# CurrentAmplifier_V2.net
KiCad netlist of a schematic drawn in EAGLE
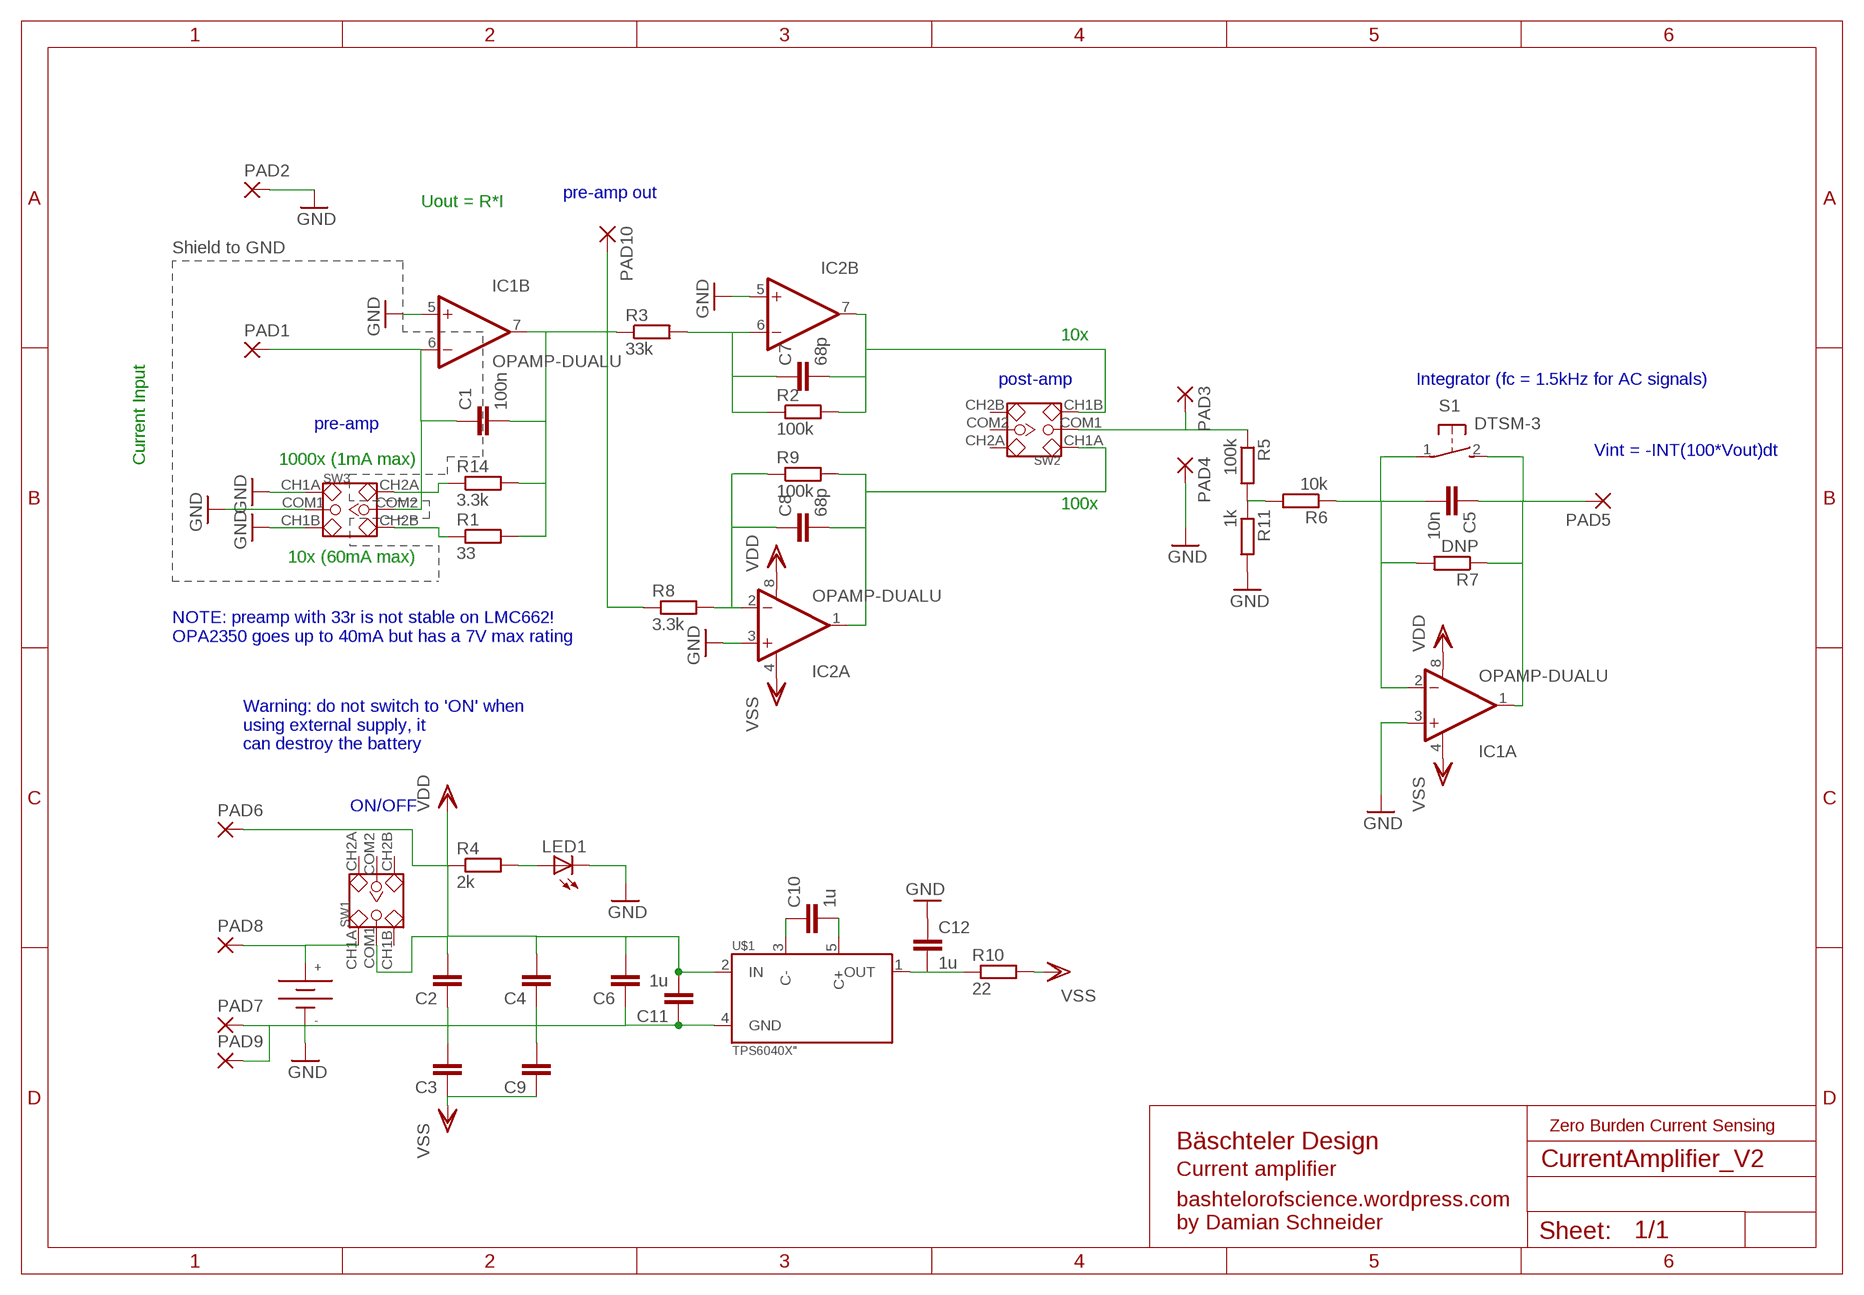
[diagram p0: schematic, sheet 1]

(export (version "E")
  (design (tool "Eeschema 10.0.6"))
  (components
    (comp (ref "C1")
      (value "100n")
      (footprint "eagle-import:C0805K")
      (libsource (lib "eagle-import") (part "C-EUC0805K"))
    )
    (comp (ref "C2")
      (value "C-EUC0805")
      (footprint "eagle-import:C0805")
      (libsource (lib "eagle-import") (part "C-EUC0805"))
    )
    (comp (ref "C3")
      (value "C-EUC0805")
      (footprint "eagle-import:C0805")
      (libsource (lib "eagle-import") (part "C-EUC0805"))
    )
    (comp (ref "C4")
      (value "C-EUC0805")
      (footprint "eagle-import:C0805")
      (libsource (lib "eagle-import") (part "C-EUC0805"))
    )
    (comp (ref "C5")
      (value "10n")
      (footprint "eagle-import:C0805K")
      (libsource (lib "eagle-import") (part "C-EUC0805K"))
    )
    (comp (ref "C6")
      (value "C-EUC1206")
      (footprint "eagle-import:C1206")
      (libsource (lib "eagle-import") (part "C-EUC1206"))
    )
    (comp (ref "C7")
      (value "68p")
      (footprint "eagle-import:C0603")
      (libsource (lib "eagle-import") (part "C-EUC0603"))
    )
    (comp (ref "C8")
      (value "68p")
      (footprint "eagle-import:C0603")
      (libsource (lib "eagle-import") (part "C-EUC0603"))
    )
    (comp (ref "C9")
      (value "C-EUC1206")
      (footprint "eagle-import:C1206")
      (libsource (lib "eagle-import") (part "C-EUC1206"))
    )
    (comp (ref "C10")
      (value "1u")
      (footprint "eagle-import:C0603")
      (libsource (lib "eagle-import") (part "C-EUC0603"))
    )
    (comp (ref "C11")
      (value "1u")
      (footprint "eagle-import:C0603")
      (libsource (lib "eagle-import") (part "C-EUC0603"))
    )
    (comp (ref "C12")
      (value "1u")
      (footprint "eagle-import:C0603")
      (libsource (lib "eagle-import") (part "C-EUC0603"))
    )
    (comp (ref "CR1")
      (value "DX_CR2032HANDSOLDER")
      (footprint "eagle-import:DX_CR2032_SMD_HANDSOLDER")
      (libsource (lib "eagle-import") (part "DX_CR2032HANDSOLDER"))
    )
    (comp (ref "IC1")
      (value "OPAMP-DUALU")
      (footprint "eagle-import:SO08")
      (libsource (lib "eagle-import") (part "OPAMP-DUALU"))
    )
    (comp (ref "IC2")
      (value "OPAMP-DUALU")
      (footprint "eagle-import:SO08")
      (libsource (lib "eagle-import") (part "OPAMP-DUALU"))
    )
    (comp (ref "LED1")
      (value "LEDCHIP-LED0805")
      (footprint "eagle-import:CHIP-LED0805")
      (libsource (lib "eagle-import") (part "LEDCHIP-LED0805"))
    )
    (comp (ref "PAD1")
      (value "1,6/0,9")
      (footprint "eagle-import:1,6_0,9")
      (libsource (lib "eagle-import") (part "1,6/0,9"))
    )
    (comp (ref "PAD2")
      (value "1,6/0,9")
      (footprint "eagle-import:1,6_0,9")
      (libsource (lib "eagle-import") (part "1,6/0,9"))
    )
    (comp (ref "PAD3")
      (value "1,6/0,9")
      (footprint "eagle-import:1,6_0,9")
      (libsource (lib "eagle-import") (part "1,6/0,9"))
    )
    (comp (ref "PAD4")
      (value "1,6/0,9")
      (footprint "eagle-import:1,6_0,9")
      (libsource (lib "eagle-import") (part "1,6/0,9"))
    )
    (comp (ref "PAD5")
      (value "1,6/0,9")
      (footprint "eagle-import:1,6_0,9")
      (libsource (lib "eagle-import") (part "1,6/0,9"))
    )
    (comp (ref "PAD6")
      (value "1,6/0,9")
      (footprint "eagle-import:1,6_0,9")
      (libsource (lib "eagle-import") (part "1,6/0,9"))
    )
    (comp (ref "PAD7")
      (value "1,6/0,9")
      (footprint "eagle-import:1,6_0,9")
      (libsource (lib "eagle-import") (part "1,6/0,9"))
    )
    (comp (ref "PAD8")
      (value "1,6/0,9")
      (footprint "eagle-import:1,6_0,9")
      (libsource (lib "eagle-import") (part "1,6/0,9"))
    )
    (comp (ref "PAD9")
      (value "1,6/0,9")
      (footprint "eagle-import:1,6_0,9")
      (libsource (lib "eagle-import") (part "1,6/0,9"))
    )
    (comp (ref "PAD10")
      (value "1,6/0,9")
      (footprint "eagle-import:1,6_0,9")
      (libsource (lib "eagle-import") (part "1,6/0,9"))
    )
    (comp (ref "R1")
      (value "33")
      (footprint "eagle-import:R0805")
      (libsource (lib "eagle-import") (part "R-EU_R0805"))
    )
    (comp (ref "R2")
      (value "100k")
      (footprint "eagle-import:R0603")
      (libsource (lib "eagle-import") (part "R-EU_R0603"))
    )
    (comp (ref "R3")
      (value "33k")
      (footprint "eagle-import:R0603")
      (libsource (lib "eagle-import") (part "R-EU_R0603"))
    )
    (comp (ref "R4")
      (value "2k")
      (footprint "eagle-import:R0603")
      (libsource (lib "eagle-import") (part "R-EU_R0603"))
    )
    (comp (ref "R5")
      (value "100k")
      (footprint "eagle-import:R0603")
      (libsource (lib "eagle-import") (part "R-EU_R0603"))
    )
    (comp (ref "R6")
      (value "10k")
      (footprint "eagle-import:R0603")
      (libsource (lib "eagle-import") (part "R-EU_R0603"))
    )
    (comp (ref "R7")
      (value "DNP")
      (footprint "eagle-import:R0805")
      (libsource (lib "eagle-import") (part "R-EU_R0805"))
    )
    (comp (ref "R8")
      (value "3.3k")
      (footprint "eagle-import:R0603")
      (libsource (lib "eagle-import") (part "R-EU_R0603"))
    )
    (comp (ref "R9")
      (value "100k")
      (footprint "eagle-import:R0603")
      (libsource (lib "eagle-import") (part "R-EU_R0603"))
    )
    (comp (ref "R10")
      (value "22")
      (footprint "eagle-import:R0805")
      (libsource (lib "eagle-import") (part "R-EU_R0805"))
    )
    (comp (ref "R11")
      (value "1k")
      (footprint "eagle-import:R0603")
      (libsource (lib "eagle-import") (part "R-EU_R0603"))
    )
    (comp (ref "R14")
      (value "3.3k")
      (footprint "eagle-import:R0805")
      (libsource (lib "eagle-import") (part "R-EU_R0805"))
    )
    (comp (ref "S1")
      (value "DTSM-3")
      (footprint "eagle-import:DTSM-3")
      (libsource (lib "eagle-import") (part "DTSM-3"))
    )
    (comp (ref "SW1")
      (value "DIP-TOGGLE-SWITCH-2CH-(2X3P-2.54)")
      (footprint "eagle-import:SW6-2.54-9.0X3.5X3.2+2.0MM")
      (fields (field (name "MPN") "MS-22D18"))
      (libsource (lib "eagle-import") (part "DIP-TOGGLE-SWITCH-2CH-(2X3P-2.54)"))
    )
    (comp (ref "SW2")
      (value "DIP-TOGGLE-SWITCH-2CH-(2X3P-2.54)")
      (footprint "eagle-import:SW6-2.54-9.0X3.5X3.2+2.0MM")
      (fields (field (name "MPN") "MS-22D18"))
      (libsource (lib "eagle-import") (part "DIP-TOGGLE-SWITCH-2CH-(2X3P-2.54)"))
    )
    (comp (ref "SW3")
      (value "DIP-TOGGLE-SWITCH-2CH-(2X3P-2.54)")
      (footprint "eagle-import:SW6-2.54-9.0X3.5X3.2+2.0MM")
      (fields (field (name "MPN") "MS-22D18"))
      (libsource (lib "eagle-import") (part "DIP-TOGGLE-SWITCH-2CH-(2X3P-2.54)"))
    )
    (comp (ref "U$1")
      (value "TPS6040X\"")
      (footprint "eagle-import:SOT23-5")
      (libsource (lib "eagle-import") (part "TPS6040X{dblquote}"))
    )
  )
  (nets
    (net (code "1") (name "GND") (class "Default")
      (node (ref "C11") (pin "1") (pinfunction "1_1") (pintype "passive"))
      (node (ref "C12") (pin "1") (pinfunction "1_1") (pintype "passive"))
      (node (ref "C2") (pin "1") (pinfunction "1_1") (pintype "passive"))
      (node (ref "C3") (pin "2") (pinfunction "2_2") (pintype "passive"))
      (node (ref "C4") (pin "1") (pinfunction "1_1") (pintype "passive"))
      (node (ref "C6") (pin "1") (pinfunction "1_1") (pintype "passive"))
      (node (ref "C9") (pin "2") (pinfunction "2_2") (pintype "passive"))
      (node (ref "CR1") (pin "P$2") (pinfunction "-_P$2") (pintype "power_in"))
      (node (ref "IC1") (pin "3") (pinfunction "+IN_3") (pintype "input"))
      (node (ref "IC1") (pin "5") (pinfunction "+IN_5") (pintype "input"))
      (node (ref "IC2") (pin "3") (pinfunction "+IN_3") (pintype "input"))
      (node (ref "IC2") (pin "5") (pinfunction "+IN_5") (pintype "input"))
      (node (ref "LED1") (pin "C") (pinfunction "C_C") (pintype "passive"))
      (node (ref "PAD2") (pin "1") (pinfunction "P_1") (pintype "passive"))
      (node (ref "PAD4") (pin "1") (pinfunction "P_1") (pintype "passive"))
      (node (ref "PAD7") (pin "1") (pinfunction "P_1") (pintype "passive"))
      (node (ref "PAD9") (pin "1") (pinfunction "P_1") (pintype "passive"))
      (node (ref "R11") (pin "2") (pinfunction "2_2") (pintype "passive"))
      (node (ref "SW3") (pin "CH1A") (pinfunction "CH1A_CH1A") (pintype "bidirectional"))
      (node (ref "SW3") (pin "CH1B") (pinfunction "CH1B_CH1B") (pintype "bidirectional"))
      (node (ref "SW3") (pin "COM1") (pinfunction "COM1_COM1") (pintype "bidirectional"))
      (node (ref "U$1") (pin "4") (pinfunction "GND_4") (pintype "bidirectional"))
    )
    (net (code "2") (name "Net-(CR1-+)") (class "Default")
      (node (ref "CR1") (pin "P$1") (pinfunction "+_P$1") (pintype "power_in"))
      (node (ref "PAD8") (pin "1") (pinfunction "P_1") (pintype "passive"))
      (node (ref "SW1") (pin "CH1A") (pinfunction "CH1A_CH1A") (pintype "bidirectional"))
    )
    (net (code "3") (name "Net-(IC1A--IN)") (class "Default")
      (node (ref "C5") (pin "2") (pinfunction "2_2") (pintype "passive"))
      (node (ref "IC1") (pin "2") (pinfunction "-IN_2") (pintype "input"))
      (node (ref "R6") (pin "1") (pinfunction "1_1") (pintype "passive"))
      (node (ref "R7") (pin "2") (pinfunction "2_2") (pintype "passive"))
      (node (ref "S1") (pin "1") (pinfunction "1_1") (pintype "passive"))
    )
    (net (code "4") (name "Net-(IC1A-OUT)") (class "Default")
      (node (ref "C5") (pin "1") (pinfunction "1_1") (pintype "passive"))
      (node (ref "IC1") (pin "1") (pinfunction "OUT_1") (pintype "output"))
      (node (ref "PAD5") (pin "1") (pinfunction "P_1") (pintype "passive"))
      (node (ref "R7") (pin "1") (pinfunction "1_1") (pintype "passive"))
      (node (ref "S1") (pin "2") (pinfunction "2_2") (pintype "passive"))
    )
    (net (code "5") (name "Net-(IC1B--IN)") (class "Default")
      (node (ref "C1") (pin "1") (pinfunction "1_1") (pintype "passive"))
      (node (ref "IC1") (pin "6") (pinfunction "-IN_6") (pintype "input"))
      (node (ref "PAD1") (pin "1") (pinfunction "P_1") (pintype "passive"))
      (node (ref "SW3") (pin "COM2") (pinfunction "COM2_COM2") (pintype "bidirectional"))
    )
    (net (code "6") (name "Net-(IC1B-OUT)") (class "Default")
      (node (ref "C1") (pin "2") (pinfunction "2_2") (pintype "passive"))
      (node (ref "IC1") (pin "7") (pinfunction "OUT_7") (pintype "output"))
      (node (ref "PAD10") (pin "1") (pinfunction "P_1") (pintype "passive"))
      (node (ref "R1") (pin "2") (pinfunction "2_2") (pintype "passive"))
      (node (ref "R14") (pin "2") (pinfunction "2_2") (pintype "passive"))
      (node (ref "R3") (pin "1") (pinfunction "1_1") (pintype "passive"))
      (node (ref "R8") (pin "1") (pinfunction "1_1") (pintype "passive"))
    )
    (net (code "7") (name "Net-(IC2A--IN)") (class "Default")
      (node (ref "C8") (pin "1") (pinfunction "1_1") (pintype "passive"))
      (node (ref "IC2") (pin "2") (pinfunction "-IN_2") (pintype "input"))
      (node (ref "R8") (pin "2") (pinfunction "2_2") (pintype "passive"))
      (node (ref "R9") (pin "1") (pinfunction "1_1") (pintype "passive"))
    )
    (net (code "8") (name "Net-(IC2A-OUT)") (class "Default")
      (node (ref "C8") (pin "2") (pinfunction "2_2") (pintype "passive"))
      (node (ref "IC2") (pin "1") (pinfunction "OUT_1") (pintype "output"))
      (node (ref "R9") (pin "2") (pinfunction "2_2") (pintype "passive"))
      (node (ref "SW2") (pin "CH1A") (pinfunction "CH1A_CH1A") (pintype "bidirectional"))
    )
    (net (code "9") (name "Net-(IC2B--IN)") (class "Default")
      (node (ref "C7") (pin "1") (pinfunction "1_1") (pintype "passive"))
      (node (ref "IC2") (pin "6") (pinfunction "-IN_6") (pintype "input"))
      (node (ref "R2") (pin "1") (pinfunction "1_1") (pintype "passive"))
      (node (ref "R3") (pin "2") (pinfunction "2_2") (pintype "passive"))
    )
    (net (code "10") (name "Net-(IC2B-OUT)") (class "Default")
      (node (ref "C7") (pin "2") (pinfunction "2_2") (pintype "passive"))
      (node (ref "IC2") (pin "7") (pinfunction "OUT_7") (pintype "output"))
      (node (ref "R2") (pin "2") (pinfunction "2_2") (pintype "passive"))
      (node (ref "SW2") (pin "CH1B") (pinfunction "CH1B_CH1B") (pintype "bidirectional"))
    )
    (net (code "11") (name "Net-(LED1-PadA)") (class "Default")
      (node (ref "LED1") (pin "A") (pinfunction "A_A") (pintype "passive"))
      (node (ref "R4") (pin "2") (pinfunction "2_2") (pintype "passive"))
    )
    (net (code "12") (name "Net-(PAD3-P)") (class "Default")
      (node (ref "PAD3") (pin "1") (pinfunction "P_1") (pintype "passive"))
      (node (ref "R5") (pin "1") (pinfunction "1_1") (pintype "passive"))
      (node (ref "SW2") (pin "COM1") (pinfunction "COM1_COM1") (pintype "bidirectional"))
    )
    (net (code "13") (name "Net-(R1-Pad1)") (class "Default")
      (node (ref "R1") (pin "1") (pinfunction "1_1") (pintype "passive"))
      (node (ref "SW3") (pin "CH2B") (pinfunction "CH2B_CH2B") (pintype "bidirectional"))
    )
    (net (code "14") (name "Net-(R11-Pad1)") (class "Default")
      (node (ref "R11") (pin "1") (pinfunction "1_1") (pintype "passive"))
      (node (ref "R5") (pin "2") (pinfunction "2_2") (pintype "passive"))
      (node (ref "R6") (pin "2") (pinfunction "2_2") (pintype "passive"))
    )
    (net (code "15") (name "Net-(R14-Pad1)") (class "Default")
      (node (ref "R14") (pin "1") (pinfunction "1_1") (pintype "passive"))
      (node (ref "SW3") (pin "CH2A") (pinfunction "CH2A_CH2A") (pintype "bidirectional"))
    )
    (net (code "16") (name "Net-(U$1-C+)") (class "Default")
      (node (ref "C10") (pin "2") (pinfunction "2_2") (pintype "passive"))
      (node (ref "U$1") (pin "5") (pinfunction "C+_5") (pintype "bidirectional"))
    )
    (net (code "17") (name "Net-(U$1-C-)") (class "Default")
      (node (ref "C10") (pin "1") (pinfunction "1_1") (pintype "passive"))
      (node (ref "U$1") (pin "3") (pinfunction "C-_3") (pintype "bidirectional"))
    )
    (net (code "18") (name "Net-(U$1-OUT)") (class "Default")
      (node (ref "C12") (pin "2") (pinfunction "2_2") (pintype "passive"))
      (node (ref "R10") (pin "1") (pinfunction "1_1") (pintype "passive"))
      (node (ref "U$1") (pin "1") (pinfunction "OUT_1") (pintype "bidirectional"))
    )
    (net (code "19") (name "VDD") (class "Default")
      (node (ref "C11") (pin "2") (pinfunction "2_2") (pintype "passive"))
      (node (ref "C2") (pin "2") (pinfunction "2_2") (pintype "passive"))
      (node (ref "C4") (pin "2") (pinfunction "2_2") (pintype "passive"))
      (node (ref "C6") (pin "2") (pinfunction "2_2") (pintype "passive"))
      (node (ref "IC1") (pin "8") (pinfunction "V+_8") (pintype "power_in"))
      (node (ref "IC2") (pin "8") (pinfunction "V+_8") (pintype "power_in"))
      (node (ref "PAD6") (pin "1") (pinfunction "P_1") (pintype "passive"))
      (node (ref "R4") (pin "1") (pinfunction "1_1") (pintype "passive"))
      (node (ref "SW1") (pin "COM1") (pinfunction "COM1_COM1") (pintype "bidirectional"))
      (node (ref "U$1") (pin "2") (pinfunction "IN_2") (pintype "bidirectional"))
    )
    (net (code "20") (name "VSS") (class "Default")
      (node (ref "C3") (pin "1") (pinfunction "1_1") (pintype "passive"))
      (node (ref "C9") (pin "1") (pinfunction "1_1") (pintype "passive"))
      (node (ref "IC1") (pin "4") (pinfunction "V-_4") (pintype "power_in"))
      (node (ref "IC2") (pin "4") (pinfunction "V-_4") (pintype "power_in"))
      (node (ref "R10") (pin "2") (pinfunction "2_2") (pintype "passive"))
    )
    (net (code "21") (name "unconnected-(SW1-PadCH1B)") (class "Default")
      (node (ref "SW1") (pin "CH1B") (pinfunction "CH1B_CH1B") (pintype "bidirectional"))
    )
    (net (code "22") (name "unconnected-(SW1-PadCH2A)") (class "Default")
      (node (ref "SW1") (pin "CH2A") (pinfunction "CH2A_CH2A") (pintype "bidirectional"))
    )
    (net (code "23") (name "unconnected-(SW1-PadCH2B)") (class "Default")
      (node (ref "SW1") (pin "CH2B") (pinfunction "CH2B_CH2B") (pintype "bidirectional"))
    )
    (net (code "24") (name "unconnected-(SW1-PadCOM2)") (class "Default")
      (node (ref "SW1") (pin "COM2") (pinfunction "COM2_COM2") (pintype "bidirectional"))
    )
    (net (code "25") (name "unconnected-(SW2-PadCH2A)") (class "Default")
      (node (ref "SW2") (pin "CH2A") (pinfunction "CH2A_CH2A") (pintype "bidirectional"))
    )
    (net (code "26") (name "unconnected-(SW2-PadCH2B)") (class "Default")
      (node (ref "SW2") (pin "CH2B") (pinfunction "CH2B_CH2B") (pintype "bidirectional"))
    )
    (net (code "27") (name "unconnected-(SW2-PadCOM2)") (class "Default")
      (node (ref "SW2") (pin "COM2") (pinfunction "COM2_COM2") (pintype "bidirectional"))
    )
  )
)
